# 4_battery_monitoring_and_switches.net
KiCad netlist of a schematic drawn in Altium Designer
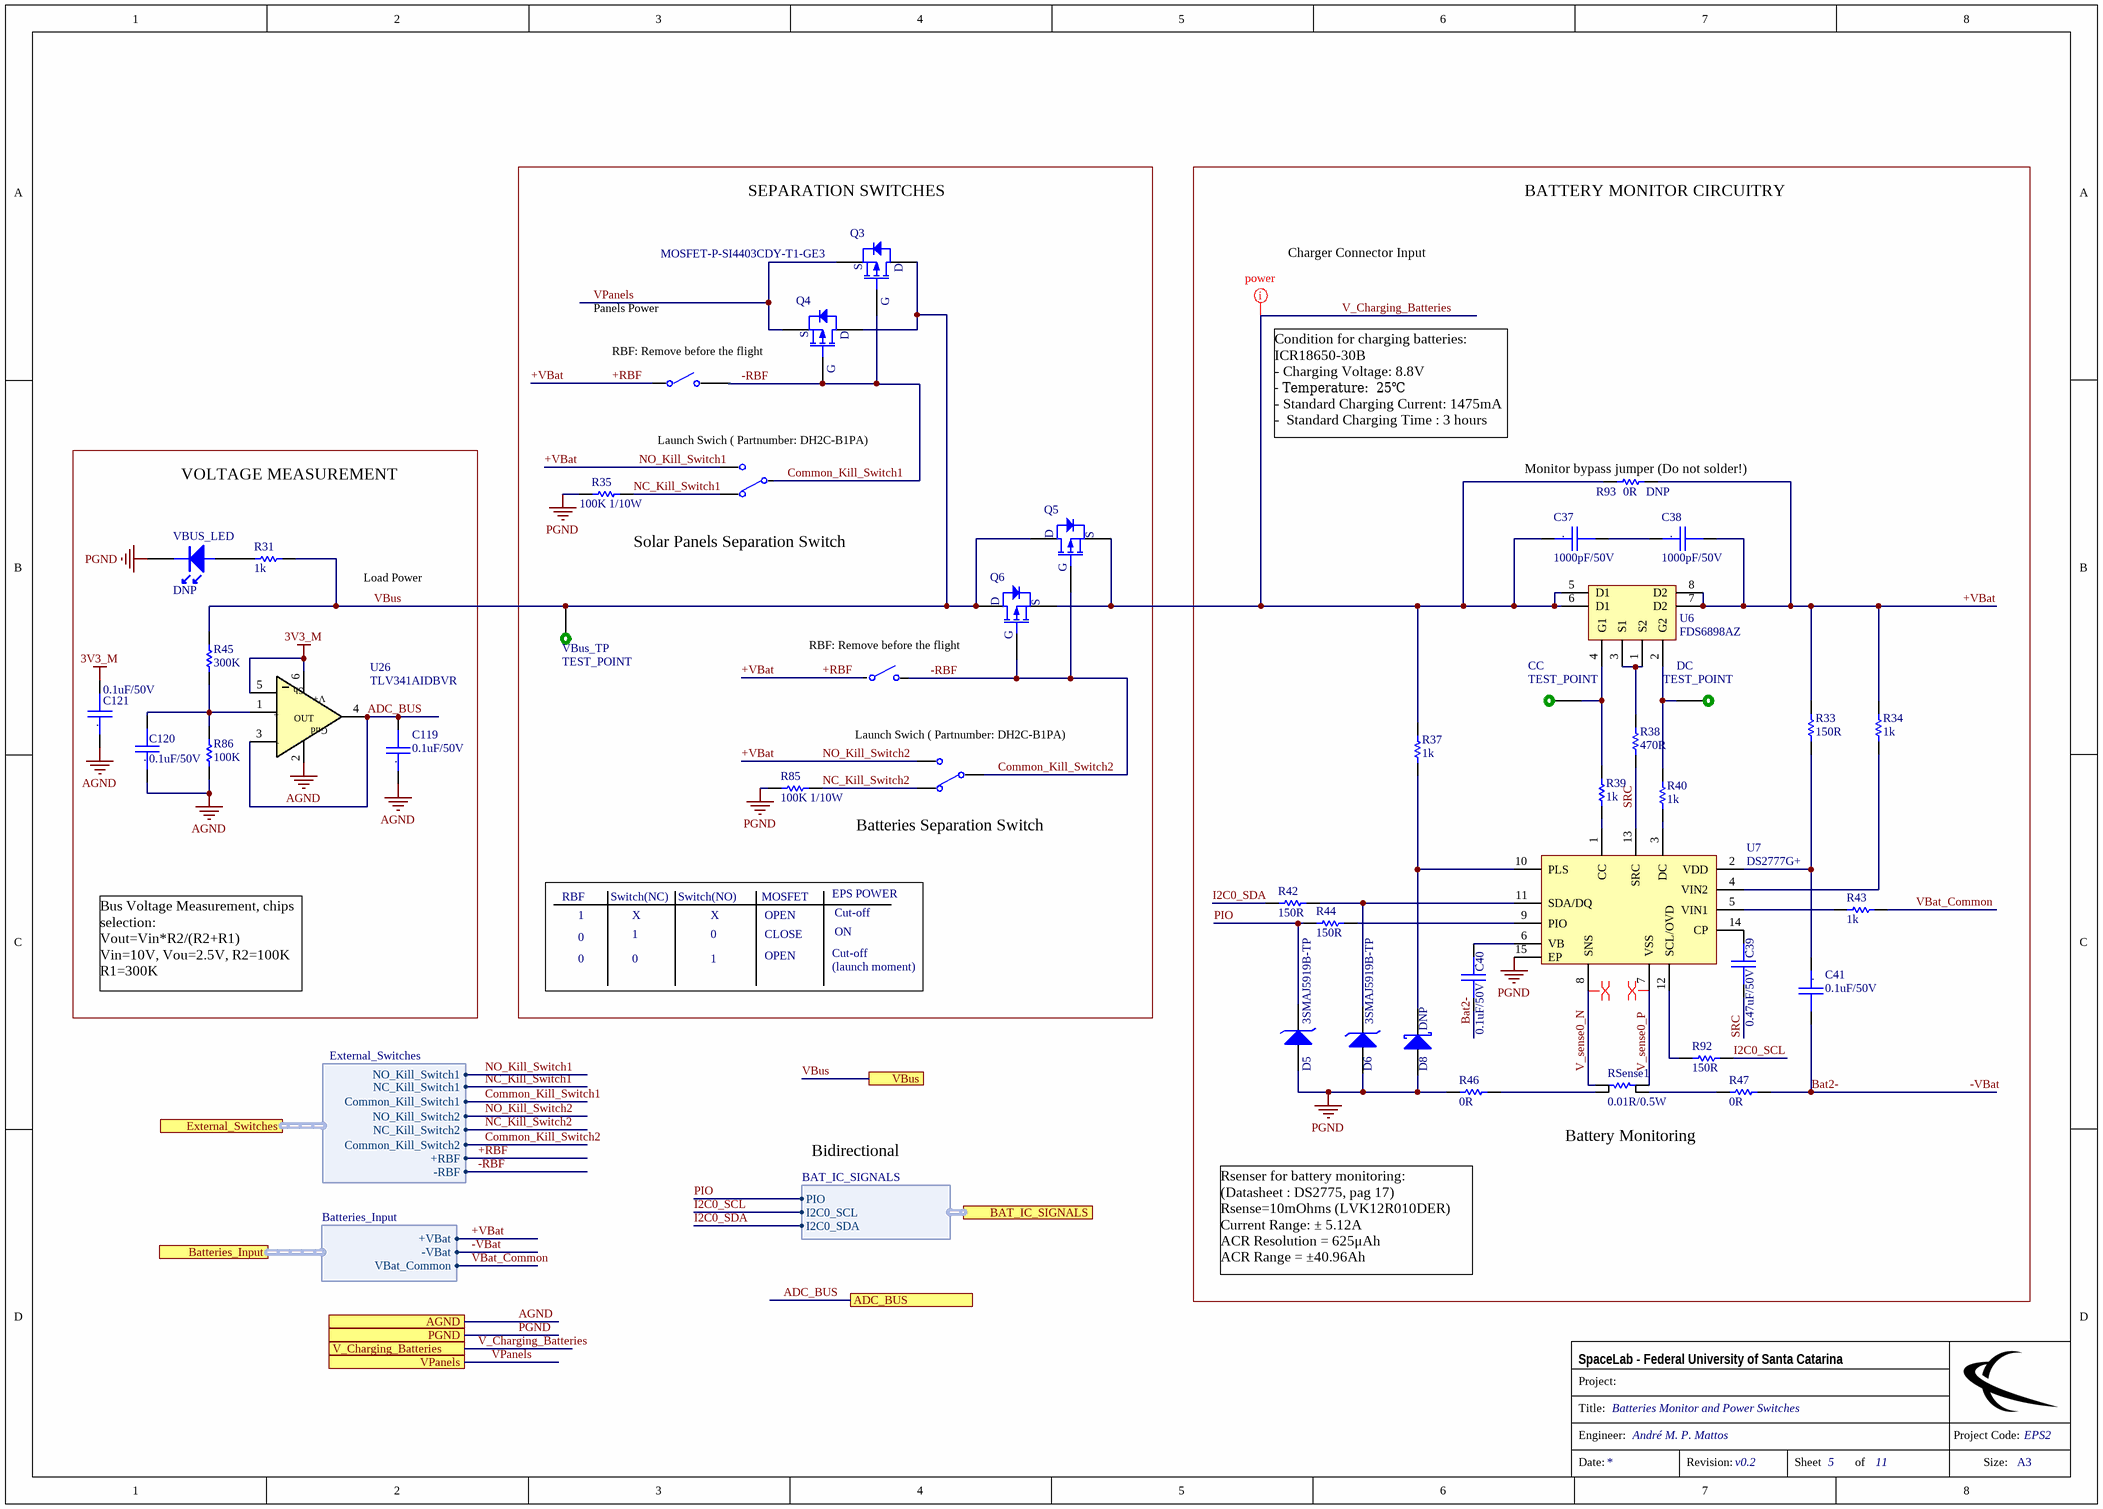
[diagram p0: 4_battery_monitoring_and_switches.schdoc]

(export (version "E")
  (design (tool "Eeschema 10.0.6"))
  (components
    (comp (ref "C37")
      (value "1000pF/50V")
      (footprint "CC0603")
      (description "CAP CER 1000pF 50V 10% X7R 0603")
      (fields (field (name "PARTNUMBER") "CC0603KRX7R9BB102") (field (name "MANUFACTURER") "Yageo"))
      (libsource (lib "PCB_Project_FlightModel_EPS") (part "Cap_Cer_X7R_1000pF_50V_0603"))
    )
    (comp (ref "C38")
      (value "1000pF/50V")
      (footprint "CC0603")
      (description "CAP CER 1000pF 50V 10% X7R 0603")
      (fields (field (name "PARTNUMBER") "CC0603KRX7R9BB102") (field (name "MANUFACTURER") "Yageo"))
      (libsource (lib "PCB_Project_FlightModel_EPS") (part "Cap_Cer_X7R_1000pF_50V_0603"))
    )
    (comp (ref "C39")
      (value "0.47uF/50V")
      (footprint "CC0603")
      (description "CAP CER 0.47UF 50V 10% X7R 0603")
      (fields (field (name "PARTNUMBER") "C1608X7R1H474K080AE") (field (name "MANUFACTURER") "TDK"))
      (libsource (lib "PCB_Project_FlightModel_EPS") (part "Cap_Cer_X7R_0.47uF_50V_0603"))
    )
    (comp (ref "C40")
      (value "0.1uF/50V")
      (footprint "CC0603")
      (description "CAP CER 0.1UF 50V 10% X7R 0603")
      (fields (field (name "PARTNUMBER") "CC0603KPX7R9BB104") (field (name "MANUFACTURER") "Yageo"))
      (libsource (lib "PCB_Project_FlightModel_EPS") (part "Cap_Cer_X7R_0.1uF_50V_0603"))
    )
    (comp (ref "C41")
      (value "0.1uF/50V")
      (footprint "CC0603")
      (description "CAP CER 0.1UF 50V 10% X7R 0603")
      (fields (field (name "PARTNUMBER") "CC0603KPX7R9BB104") (field (name "MANUFACTURER") "Yageo"))
      (libsource (lib "PCB_Project_FlightModel_EPS") (part "Cap_Cer_X7R_0.1uF_50V_0603"))
    )
    (comp (ref "C119")
      (value "0.1uF/50V")
      (footprint "CC0603")
      (description "CAP CER 0.1UF 50V 10% X7R 0603")
      (fields (field (name "PARTNUMBER") "CC0603KPX7R9BB104") (field (name "MANUFACTURER") "Yageo"))
      (libsource (lib "PCB_Project_FlightModel_EPS") (part "Cap_Cer_X7R_0.1uF_50V_0603"))
    )
    (comp (ref "C120")
      (value "0.1uF/50V")
      (footprint "CC0603")
      (description "CAP CER 0.1UF 50V 10% X7R 0603")
      (fields (field (name "PARTNUMBER") "CC0603KPX7R9BB104") (field (name "MANUFACTURER") "Yageo"))
      (libsource (lib "PCB_Project_FlightModel_EPS") (part "Cap_Cer_X7R_0.1uF_50V_0603"))
    )
    (comp (ref "C121")
      (value "0.1uF/50V")
      (footprint "CC0603")
      (description "CAP CER 0.1UF 50V 10% X7R 0603")
      (fields (field (name "PARTNUMBER") "CC0603KPX7R9BB104") (field (name "MANUFACTURER") "Yageo"))
      (libsource (lib "PCB_Project_FlightModel_EPS") (part "Cap_Cer_X7R_0.1uF_50V_0603"))
    )
    (comp (ref "CC")
      (value "TEST_POINT")
      (footprint "TEST_POINT")
      (description "Test point")
      (libsource (lib "PCB_Project_FlightModel_EPS") (part "TEST_POINT"))
    )
    (comp (ref "D5")
      (value "3SMAJ5919B-TP")
      (footprint "DO-214AC")
      (description "DIODE ZENER 5.6V 3W DO214AC")
      (fields (field (name "MANUFACTURER") "MCC") (field (name "TOLERANCE") "5%"))
      (libsource (lib "PCB_Project_FlightModel_EPS") (part "DIODE_ZENER_5.6V_3SMAJ5919B"))
    )
    (comp (ref "D6")
      (value "3SMAJ5919B-TP")
      (footprint "DO-214AC")
      (description "DIODE ZENER 5.6V 3W DO214AC")
      (fields (field (name "MANUFACTURER") "MCC") (field (name "TOLERANCE") "5%"))
      (libsource (lib "PCB_Project_FlightModel_EPS") (part "DIODE_ZENER_5.6V_3SMAJ5919B"))
    )
    (comp (ref "D8")
      (value "DNP")
      (footprint "SOD323F")
      (description "DIODE SCHOTTKY 23V 1A SOD323F")
      (fields (field (name "PARTNUMBER") "NSVR0320MW2T1G") (field (name "MANUFACTURER") "ON Semiconductor"))
      (libsource (lib "PCB_Project_FlightModel_EPS") (part "DIODE_SCHOTTKY_23V_1A_NSVR0320MW2T1G"))
    )
    (comp (ref "DC")
      (value "TEST_POINT")
      (footprint "TEST_POINT")
      (description "Test point")
      (libsource (lib "PCB_Project_FlightModel_EPS") (part "TEST_POINT"))
    )
    (comp (ref "Q3")
      (value "MOSFET-P-SI4403CDY-T1-GE3")
      (footprint "SOIC8_Mosfet")
      (description "MOSFET 1.8V P-Channel 20 V, 0.0155 Ω typ., 13.4 A")
      (fields
        (field (name "PARTNUMBER") "SI4403CDY-T1-GE3")
        (field (name "MANUFACTURER") "Vishay Siliconix")
        (field (name "PUBLISHER") "Altium Limited")
      )
      (libsource (lib "PCB_Project_FlightModel_EPS") (part "MOSFET-P- SI4403CDY-T1-GE3"))
    )
    (comp (ref "Q4")
      (value "MOSFET-P-SI4403CDY-T1-GE3")
      (footprint "SOIC8_Mosfet")
      (description "MOSFET 1.8V P-Channel 20 V, 0.0155 Ω typ., 13.4 A")
      (fields
        (field (name "PARTNUMBER") "SI4403CDY-T1-GE3")
        (field (name "MANUFACTURER") "Vishay Siliconix")
        (field (name "PUBLISHER") "Altium Limited")
      )
      (libsource (lib "PCB_Project_FlightModel_EPS") (part "MOSFET-P- SI4403CDY-T1-GE3"))
    )
    (comp (ref "Q5")
      (value "MOSFET-P-SI4403CDY-T1-GE3")
      (footprint "SOIC8_Mosfet")
      (description "MOSFET 1.8V P-Channel 20 V, 0.0155 Ω typ., 13.4 A")
      (fields
        (field (name "PARTNUMBER") "SI4403CDY-T1-GE3")
        (field (name "MANUFACTURER") "Vishay Siliconix")
        (field (name "PUBLISHER") "Altium Limited")
      )
      (libsource (lib "PCB_Project_FlightModel_EPS") (part "MOSFET-P- SI4403CDY-T1-GE3"))
    )
    (comp (ref "Q6")
      (value "MOSFET-P-SI4403CDY-T1-GE3")
      (footprint "SOIC8_Mosfet")
      (description "MOSFET 1.8V P-Channel 20 V, 0.0155 Ω typ., 13.4 A")
      (fields
        (field (name "PARTNUMBER") "SI4403CDY-T1-GE3")
        (field (name "MANUFACTURER") "Vishay Siliconix")
        (field (name "PUBLISHER") "Altium Limited")
      )
      (libsource (lib "PCB_Project_FlightModel_EPS") (part "MOSFET-P- SI4403CDY-T1-GE3"))
    )
    (comp (ref "R31")
      (value "1k")
      (footprint "0603")
      (description "RES 1.0K OHM 1/8W 1% 0603")
      (fields (field (name "PARTNUMBER") "MCT06030C1001FP500") (field (name "MANUFACTURER") "Vishay"))
      (libsource (lib "PCB_Project_FlightModel_EPS") (part "R1.0k_1%_1/8W_0603"))
    )
    (comp (ref "R33")
      (value "150R")
      (footprint "0603")
      (description "RES 150R OHM 1/10W 1% 0603")
      (fields (field (name "PARTNUMBER") "CRCW0603150RFKEA") (field (name "MANUFACTURER") "Vishay"))
      (libsource (lib "PCB_Project_FlightModel_EPS") (part "R150R_1%_1/10W_0603"))
    )
    (comp (ref "R34")
      (value "1k")
      (footprint "0603")
      (description "RES 1.0K OHM 1/8W 1% 0603")
      (fields (field (name "PARTNUMBER") "MCT06030C1001FP500") (field (name "MANUFACTURER") "Vishay"))
      (libsource (lib "PCB_Project_FlightModel_EPS") (part "R1.0k_1%_1/8W_0603"))
    )
    (comp (ref "R35")
      (value "100K 1/10W")
      (footprint "0805")
      (description "RES 100K OHM 1/10W 0.1% 0805")
      (fields (field (name "PARTNUMBER") "CPF-A-0805B100KE") (field (name "MANUFACTURER") "TE Connectivity"))
      (libsource (lib "PCB_Project_FlightModel_EPS") (part "R100k_0.1%_1/10W_0805"))
    )
    (comp (ref "R37")
      (value "1k")
      (footprint "0603")
      (description "RES 1.0K OHM 1/8W 1% 0603")
      (fields (field (name "PARTNUMBER") "MCT06030C1001FP500") (field (name "MANUFACTURER") "Vishay"))
      (libsource (lib "PCB_Project_FlightModel_EPS") (part "R1.0k_1%_1/8W_0603"))
    )
    (comp (ref "R38")
      (value "470R")
      (footprint "0603")
      (description "RES 470R OHM 1/8W 1% 0603")
      (fields
        (field (name "PARTNUMBER") "MCT06030C4700FP500")
        (field (name "MANUFACTURER") "Vishay Beyschlag")
      )
      (libsource (lib "PCB_Project_FlightModel_EPS") (part "R470R_1%_1/8W_0603"))
    )
    (comp (ref "R39")
      (value "1k")
      (footprint "0603")
      (description "RES 1.0K OHM 1/8W 1% 0603")
      (fields (field (name "PARTNUMBER") "MCT06030C1001FP500") (field (name "MANUFACTURER") "Vishay"))
      (libsource (lib "PCB_Project_FlightModel_EPS") (part "R1.0k_1%_1/8W_0603"))
    )
    (comp (ref "R40")
      (value "1k")
      (footprint "0603")
      (description "RES 1.0K OHM 1/8W 1% 0603")
      (fields (field (name "PARTNUMBER") "MCT06030C1001FP500") (field (name "MANUFACTURER") "Vishay"))
      (libsource (lib "PCB_Project_FlightModel_EPS") (part "R1.0k_1%_1/8W_0603"))
    )
    (comp (ref "R42")
      (value "150R")
      (footprint "0603")
      (description "RES 150R OHM 1/10W 1% 0603")
      (fields (field (name "PARTNUMBER") "CRCW0603150RFKEA") (field (name "MANUFACTURER") "Vishay"))
      (libsource (lib "PCB_Project_FlightModel_EPS") (part "R150R_1%_1/10W_0603"))
    )
    (comp (ref "R43")
      (value "1k")
      (footprint "0603")
      (description "RES 1.0K OHM 1/8W 1% 0603")
      (fields (field (name "PARTNUMBER") "MCT06030C1001FP500") (field (name "MANUFACTURER") "Vishay"))
      (libsource (lib "PCB_Project_FlightModel_EPS") (part "R1.0k_1%_1/8W_0603"))
    )
    (comp (ref "R44")
      (value "150R")
      (footprint "0603")
      (description "RES 150R OHM 1/10W 1% 0603")
      (fields (field (name "PARTNUMBER") "CRCW0603150RFKEA") (field (name "MANUFACTURER") "Vishay"))
      (libsource (lib "PCB_Project_FlightModel_EPS") (part "R150R_1%_1/10W_0603"))
    )
    (comp (ref "R45")
      (value "300K")
      (footprint "0603")
      (description "RES 300K OHM 1/10W 0.1% 0603")
      (fields (field (name "PARTNUMBER") "RG1608P-304-B-T5") (field (name "MANUFACTURER") "Susumu"))
      (libsource (lib "PCB_Project_FlightModel_EPS") (part "R300K_0.1%_1/10W_0603"))
    )
    (comp (ref "R46")
      (value "0R")
      (footprint "1206")
      (description "RES 0.0 OHM 3/4W JUMP 1206")
      (fields
        (field (name "PARTNUMBER") "HCJ1206ZT0R00")
        (field (name "MANUFACTURER") "Stackpole Electronics")
      )
      (libsource (lib "PCB_Project_FlightModel_EPS") (part "R0R_JUMPER_3/4W_1206"))
    )
    (comp (ref "R47")
      (value "0R")
      (footprint "1206")
      (description "RES 0.0 OHM 3/4W JUMP 1206")
      (fields
        (field (name "PARTNUMBER") "HCJ1206ZT0R00")
        (field (name "MANUFACTURER") "Stackpole Electronics")
      )
      (libsource (lib "PCB_Project_FlightModel_EPS") (part "R0R_JUMPER_3/4W_1206"))
    )
    (comp (ref "R85")
      (value "100K 1/10W")
      (footprint "0805")
      (description "RES 100K OHM 1/10W 0.1% 0805")
      (fields (field (name "PARTNUMBER") "CPF-A-0805B100KE") (field (name "MANUFACTURER") "TE Connectivity"))
      (libsource (lib "PCB_Project_FlightModel_EPS") (part "R100k_0.1%_1/10W_0805"))
    )
    (comp (ref "R86")
      (value "100K")
      (footprint "0603")
      (description "RES 100K OHM 1/10W 1% 0603")
      (fields (field (name "PARTNUMBER") "CRCW0603100KFKEA") (field (name "MANUFACTURER") "Vishay"))
      (libsource (lib "PCB_Project_FlightModel_EPS") (part "R100K_1%_1/10W_0603"))
    )
    (comp (ref "R92")
      (value "150R")
      (footprint "R0603")
      (description "RES 150R OHM 1/10W 1% 0603")
      (fields (field (name "PARTNUMBER") "CRCW0603150RFKEA") (field (name "MANUFACTURER") "Vishay"))
      (libsource (lib "schematics_library_legacy") (part "R150R_1%_1/10W_0603"))
    )
    (comp (ref "R93")
      (value "0R")
      (footprint "1206")
      (description "RES 0.0 OHM 3/4W JUMP 1206")
      (fields
        (field (name "PARTNUMBER") "HCJ1206ZT0R00")
        (field (name "MANUFACTURER") "Stackpole Electronics")
      )
      (libsource (lib "PCB_Project_FlightModel_EPS") (part "R0R_JUMPER_3/4W_1206"))
    )
    (comp (ref "RSense1")
      (value "0.01R/0.5W")
      (footprint "1206 - ohmite")
      (description "Current Sense Resistors - SMD 0.01ohm .5% 4 Terminal")
      (fields (field (name "PARTNUMBER") "LVK12R010DER") (field (name "MANUFACTURER") "Ohmite"))
      (libsource (lib "PCB_Project_FlightModel_EPS") (part "R0.01R_0.5%_0.5W_1206_4_terminal"))
    )
    (comp (ref "U6")
      (value "FDS6898AZ")
      (footprint "SOIC8")
      (description "MOSFET 2N-CH 20V 9.4A 8SOIC")
      (fields (field (name "MANUFACTURER") "ON Semiconductor / Fairchild"))
      (libsource (lib "PCB_Project_FlightModel_EPS") (part "FDS6898AZ"))
    )
    (comp (ref "U7")
      (value "DS2777G+")
      (footprint "TDFN-14-EP_3x5")
      (fields (field (name "MANUFACTURER") "Maxim") (field (name "MANUFACTURER PART NUMBER") "DS2775G+"))
      (libsource (lib "schematics_library_legacy") (part "DS2777G+"))
    )
    (comp (ref "U26")
      (value "TLV341AIDBVR")
      (footprint "SOT-23 6L")
      (fields (field (name "MANUFACTURER") "Texas Instruments"))
      (libsource (lib "PCB_Project_FlightModel_EPS") (part "TLV341AIDBVR"))
    )
    (comp (ref "VBUS_LED")
      (value "DNP")
      (footprint "0603-LED")
      (description "SMD Green LED")
      (fields (field (name "PARTNUMBER") "150060VS75000") (field (name "MANUFACTURER") "Wurth Electronics"))
      (libsource (lib "PCB_Project_FlightModel_EPS") (part "LED/G_0603"))
    )
    (comp (ref "VBus_TP")
      (value "TEST_POINT")
      (footprint "TEST_POINT")
      (description "Test point")
      (libsource (lib "PCB_Project_FlightModel_EPS") (part "TEST_POINT"))
    )
  )
  (nets
    (net (code "4") (name "/+RBF") (class "Default")
      (node (ref "C38") (pin "2") (pinfunction "2_2") (pintype "passive"))
      (node (ref "R33") (pin "1") (pinfunction "1_1") (pintype "passive"))
      (node (ref "R34") (pin "2") (pinfunction "2_2") (pintype "passive"))
      (node (ref "R93") (pin "1") (pinfunction "1_1") (pintype "passive"))
      (node (ref "U6") (pin "7") (pinfunction "D2_7") (pintype "passive"))
      (node (ref "U6") (pin "8") (pinfunction "D2_8") (pintype "passive"))
    )
    (net (code "5") (name "/-RBF") (class "Default")
      (node (ref "Q3") (pin "2") (pinfunction "G_2") (pintype "passive"))
      (node (ref "Q4") (pin "2") (pinfunction "G_2") (pintype "passive"))
      (node (ref "Q5") (pin "2") (pinfunction "G_2") (pintype "passive"))
      (node (ref "Q6") (pin "2") (pinfunction "G_2") (pintype "passive"))
    )
    (net (code "6") (name "/-VBat") (class "Default")
      (node (ref "C40") (pin "2") (pinfunction "2_2") (pintype "passive"))
      (node (ref "C41") (pin "2") (pinfunction "2_2") (pintype "passive"))
      (node (ref "R47") (pin "1") (pinfunction "1_1") (pintype "passive"))
    )
    (net (code "7") (name "/ADC_BUS") (class "Default")
      (node (ref "C119") (pin "2") (pinfunction "2_2") (pintype "passive"))
      (node (ref "U26") (pin "3") (pinfunction "-IN_3") (pintype "passive"))
      (node (ref "U26") (pin "4") (pinfunction "OUT_4") (pintype "passive"))
    )
    (net (code "8") (name "/I2C0_SCL") (class "Default")
      (node (ref "R92") (pin "1") (pinfunction "1_1") (pintype "passive"))
    )
    (net (code "9") (name "/I2C0_SDA") (class "Default")
      (node (ref "R42") (pin "2") (pinfunction "2_2") (pintype "passive"))
    )
    (net (code "10") (name "/NC_Kill_Switch1") (class "Default")
      (node (ref "R35") (pin "1") (pinfunction "1_1") (pintype "passive"))
    )
    (net (code "11") (name "/NC_Kill_Switch2") (class "Default")
      (node (ref "R85") (pin "1") (pinfunction "1_1") (pintype "passive"))
    )
    (net (code "12") (name "/PIO") (class "Default")
      (node (ref "D5") (pin "1") (pinfunction "K_1") (pintype "passive"))
      (node (ref "R44") (pin "2") (pinfunction "2_2") (pintype "passive"))
    )
    (net (code "13") (name "/SRC") (class "Default")
      (node (ref "C39") (pin "2") (pinfunction "2_2") (pintype "passive"))
      (node (ref "R38") (pin "1") (pinfunction "1_1") (pintype "passive"))
      (node (ref "U7") (pin "13") (pinfunction "SRC_13") (pintype "passive"))
    )
    (net (code "14") (name "/VBat_Common") (class "Default")
      (node (ref "R43") (pin "1") (pinfunction "1_1") (pintype "passive"))
    )
    (net (code "15") (name "/VBus") (class "Default")
      (node (ref "Q3") (pin "3") (pinfunction "D_3") (pintype "passive"))
      (node (ref "Q4") (pin "3") (pinfunction "D_3") (pintype "passive"))
      (node (ref "Q5") (pin "3") (pinfunction "D_3") (pintype "passive"))
      (node (ref "Q6") (pin "3") (pinfunction "D_3") (pintype "passive"))
      (node (ref "R31") (pin "1") (pinfunction "1_1") (pintype "passive"))
      (node (ref "R45") (pin "2") (pinfunction "2_2") (pintype "passive"))
      (node (ref "VBus_TP") (pin "1") (pinfunction "1_1") (pintype "passive"))
    )
    (net (code "16") (name "/VPanels") (class "Default")
      (node (ref "Q3") (pin "1") (pinfunction "S_1") (pintype "passive"))
      (node (ref "Q4") (pin "1") (pinfunction "S_1") (pintype "passive"))
    )
    (net (code "17") (name "/V_Charging_Batteries") (class "Default")
      (node (ref "C37") (pin "1") (pinfunction "1_1") (pintype "passive"))
      (node (ref "Q5") (pin "1") (pinfunction "S_1") (pintype "passive"))
      (node (ref "Q6") (pin "1") (pinfunction "S_1") (pintype "passive"))
      (node (ref "R37") (pin "2") (pinfunction "2_2") (pintype "passive"))
      (node (ref "R93") (pin "2") (pinfunction "2_2") (pintype "passive"))
      (node (ref "U6") (pin "5") (pinfunction "D1_5") (pintype "passive"))
      (node (ref "U6") (pin "6") (pinfunction "D1_6") (pintype "passive"))
    )
    (net (code "18") (name "/V_sense0_N") (class "Default")
      (node (ref "RSense1") (pin "2") (pinfunction "2_2") (pintype "passive"))
      (node (ref "U7") (pin "8") (pinfunction "SNS_8") (pintype "passive"))
    )
    (net (code "19") (name "/V_sense0_P") (class "Default")
      (node (ref "RSense1") (pin "1") (pinfunction "1_1") (pintype "passive"))
      (node (ref "U7") (pin "7") (pinfunction "VSS_7") (pintype "passive"))
    )
    (net (code "23") (name "3V3_M") (class "Default")
      (node (ref "C121") (pin "2") (pinfunction "2_2") (pintype "passive"))
      (node (ref "U26") (pin "5") (pinfunction "EN_5") (pintype "passive"))
      (node (ref "U26") (pin "6") (pinfunction "V+_6") (pintype "passive"))
    )
    (net (code "24") (name "AGND") (class "Default")
      (node (ref "C119") (pin "1") (pinfunction "1_1") (pintype "passive"))
      (node (ref "C120") (pin "1") (pinfunction "1_1") (pintype "passive"))
      (node (ref "C121") (pin "1") (pinfunction "1_1") (pintype "passive"))
      (node (ref "R86") (pin "1") (pinfunction "1_1") (pintype "passive"))
      (node (ref "U26") (pin "2") (pinfunction "Gnd_2") (pintype "passive"))
    )
    (net (code "25") (name "Net-(C37-Pad2)") (class "Default")
      (node (ref "C37") (pin "2") (pinfunction "2_2") (pintype "passive"))
      (node (ref "C38") (pin "1") (pinfunction "1_1") (pintype "passive"))
    )
    (net (code "26") (name "Net-(D6-K)") (class "Default")
      (node (ref "D6") (pin "1") (pinfunction "K_1") (pintype "passive"))
      (node (ref "R42") (pin "1") (pinfunction "1_1") (pintype "passive"))
      (node (ref "U7") (pin "11") (pinfunction "SDA/DQ_11") (pintype "passive"))
    )
    (net (code "27") (name "Net-(D8-K)") (class "Default")
      (node (ref "D8") (pin "1") (pinfunction "K_1") (pintype "passive"))
      (node (ref "R37") (pin "1") (pinfunction "1_1") (pintype "passive"))
      (node (ref "U7") (pin "10") (pinfunction "PLS_10") (pintype "passive"))
    )
    (net (code "28") (name "Net-(R46-Pad1)") (class "Default")
      (node (ref "R46") (pin "1") (pinfunction "1_1") (pintype "passive"))
      (node (ref "RSense1") (pin "4") (pinfunction "4_4") (pintype "passive"))
    )
    (net (code "29") (name "Net-(R47-Pad2)") (class "Default")
      (node (ref "R47") (pin "2") (pinfunction "2_2") (pintype "passive"))
      (node (ref "RSense1") (pin "3") (pinfunction "3_3") (pintype "passive"))
    )
    (net (code "30") (name "Net-(U6-G1)") (class "Default")
      (node (ref "CC") (pin "1") (pinfunction "1_1") (pintype "passive"))
      (node (ref "R39") (pin "2") (pinfunction "2_2") (pintype "passive"))
      (node (ref "U6") (pin "4") (pinfunction "G1_4") (pintype "passive"))
    )
    (net (code "31") (name "Net-(U6-G2)") (class "Default")
      (node (ref "DC") (pin "1") (pinfunction "1_1") (pintype "passive"))
      (node (ref "R40") (pin "2") (pinfunction "2_2") (pintype "passive"))
      (node (ref "U6") (pin "2") (pinfunction "G2_2") (pintype "passive"))
    )
    (net (code "32") (name "Net-(U6-S1)") (class "Default")
      (node (ref "R38") (pin "2") (pinfunction "2_2") (pintype "passive"))
      (node (ref "U6") (pin "1") (pinfunction "S2_1") (pintype "passive"))
      (node (ref "U6") (pin "3") (pinfunction "S1_3") (pintype "passive"))
    )
    (net (code "33") (name "Net-(U7-CC)") (class "Default")
      (node (ref "R39") (pin "1") (pinfunction "1_1") (pintype "passive"))
      (node (ref "U7") (pin "1") (pinfunction "CC_1") (pintype "passive"))
    )
    (net (code "34") (name "Net-(U7-CP)") (class "Default")
      (node (ref "C39") (pin "1") (pinfunction "1_1") (pintype "passive"))
      (node (ref "U7") (pin "14") (pinfunction "CP_14") (pintype "passive"))
    )
    (net (code "35") (name "Net-(U7-DC)") (class "Default")
      (node (ref "R40") (pin "1") (pinfunction "1_1") (pintype "passive"))
      (node (ref "U7") (pin "3") (pinfunction "DC_3") (pintype "passive"))
    )
    (net (code "36") (name "Net-(U7-PIO)") (class "Default")
      (node (ref "R44") (pin "1") (pinfunction "1_1") (pintype "passive"))
      (node (ref "U7") (pin "9") (pinfunction "PIO_9") (pintype "passive"))
    )
    (net (code "37") (name "Net-(U7-SCL{slash}OVD)") (class "Default")
      (node (ref "R92") (pin "2") (pinfunction "2_2") (pintype "passive"))
      (node (ref "U7") (pin "12") (pinfunction "SCL/OVD_12") (pintype "passive"))
    )
    (net (code "38") (name "Net-(U7-VB)") (class "Default")
      (node (ref "C40") (pin "1") (pinfunction "1_1") (pintype "passive"))
      (node (ref "U7") (pin "6") (pinfunction "VB_6") (pintype "passive"))
    )
    (net (code "39") (name "Net-(U7-VDD)") (class "Default")
      (node (ref "C41") (pin "1") (pinfunction "1_1") (pintype "passive"))
      (node (ref "R33") (pin "2") (pinfunction "2_2") (pintype "passive"))
      (node (ref "U7") (pin "2") (pinfunction "VDD_2") (pintype "passive"))
    )
    (net (code "40") (name "Net-(U7-VIN1)") (class "Default")
      (node (ref "R43") (pin "2") (pinfunction "2_2") (pintype "passive"))
      (node (ref "U7") (pin "5") (pinfunction "VIN1_5") (pintype "passive"))
    )
    (net (code "41") (name "Net-(U7-VIN2)") (class "Default")
      (node (ref "R34") (pin "1") (pinfunction "1_1") (pintype "passive"))
      (node (ref "U7") (pin "4") (pinfunction "VIN2_4") (pintype "passive"))
    )
    (net (code "42") (name "Net-(U26-+IN)") (class "Default")
      (node (ref "C120") (pin "2") (pinfunction "2_2") (pintype "passive"))
      (node (ref "R45") (pin "1") (pinfunction "1_1") (pintype "passive"))
      (node (ref "R86") (pin "2") (pinfunction "2_2") (pintype "passive"))
      (node (ref "U26") (pin "1") (pinfunction "+IN_1") (pintype "passive"))
    )
    (net (code "43") (name "Net-(VBUS_LED-A)") (class "Default")
      (node (ref "R31") (pin "2") (pinfunction "2_2") (pintype "passive"))
      (node (ref "VBUS_LED") (pin "1") (pinfunction "A_1") (pintype "passive"))
    )
    (net (code "44") (name "PGND") (class "Default")
      (node (ref "D5") (pin "2") (pinfunction "A_2") (pintype "passive"))
      (node (ref "D6") (pin "2") (pinfunction "A_2") (pintype "passive"))
      (node (ref "D8") (pin "2") (pinfunction "A_2") (pintype "passive"))
      (node (ref "R35") (pin "2") (pinfunction "2_2") (pintype "passive"))
      (node (ref "R46") (pin "2") (pinfunction "2_2") (pintype "passive"))
      (node (ref "R85") (pin "2") (pinfunction "2_2") (pintype "passive"))
      (node (ref "U7") (pin "15") (pinfunction "EP_15") (pintype "passive"))
      (node (ref "VBUS_LED") (pin "2") (pinfunction "K_2") (pintype "passive"))
    )
  )
)
